# LedEsp32_rev1.net
KiCad netlist of a schematic drawn in EAGLE
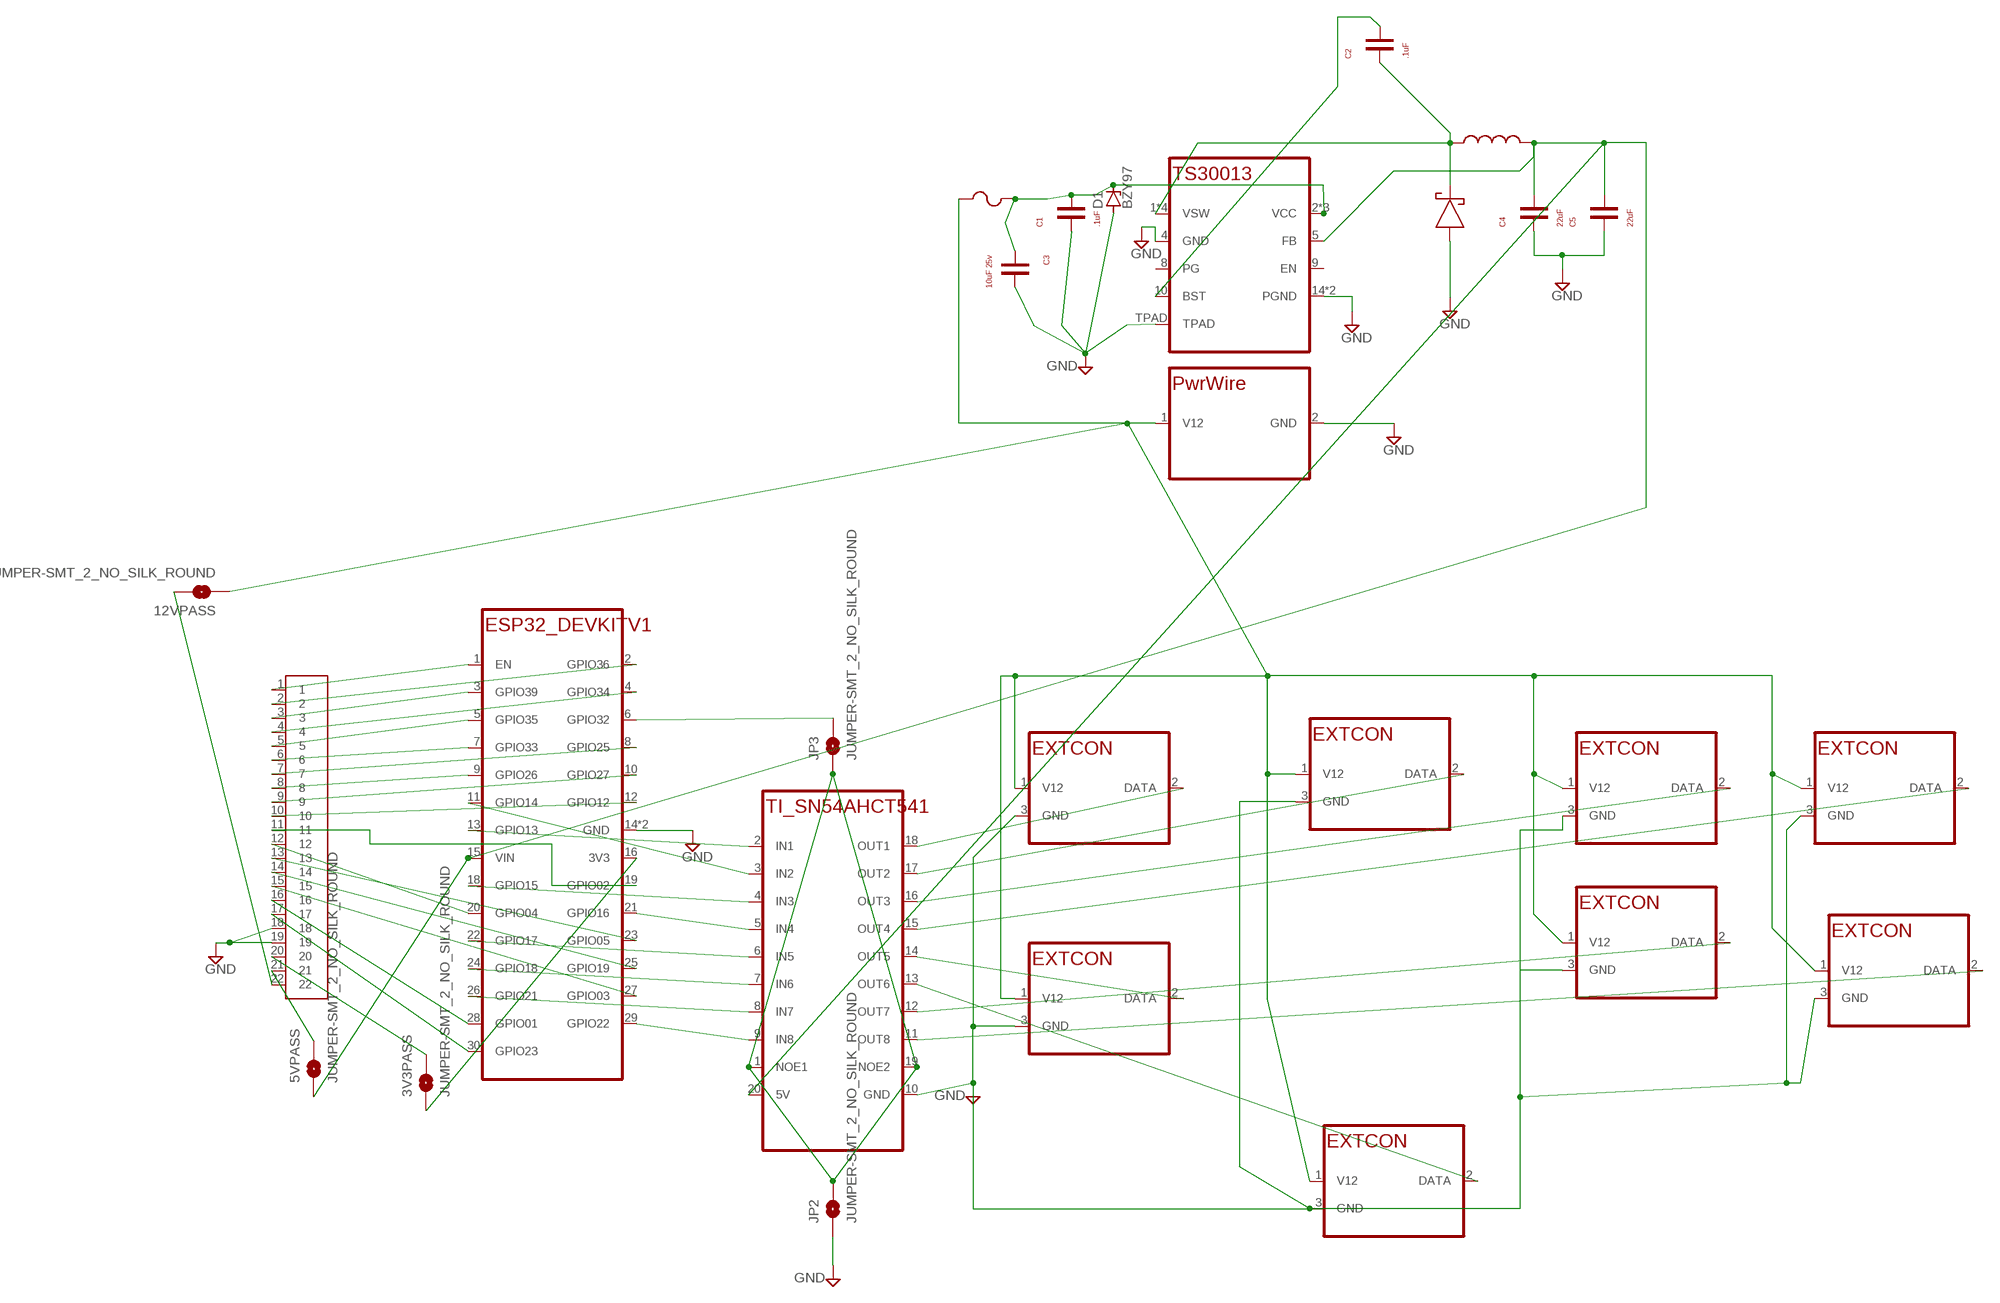
[diagram p0: schematic, sheet 1]

(export (version "E")
  (design (tool "Eeschema 10.0.6"))
  (components
    (comp (ref "3V3PASS")
      (value "JUMPER-SMT_2_NO_SILK_ROUND")
      (footprint "eagle-import:SMT-JUMPER_2_NO_SILK_ROUND")
      (libsource (lib "eagle-import") (part "JUMPER-SMT_2_NO_SILK_ROUND"))
    )
    (comp (ref "5VPASS")
      (value "JUMPER-SMT_2_NO_SILK_ROUND")
      (footprint "eagle-import:SMT-JUMPER_2_NO_SILK_ROUND")
      (libsource (lib "eagle-import") (part "JUMPER-SMT_2_NO_SILK_ROUND"))
    )
    (comp (ref "12VPASS")
      (value "JUMPER-SMT_2_NO_SILK_ROUND")
      (footprint "eagle-import:SMT-JUMPER_2_NO_SILK_ROUND")
      (libsource (lib "eagle-import") (part "JUMPER-SMT_2_NO_SILK_ROUND"))
    )
    (comp (ref "C1")
      (value ".1uF")
      (footprint "eagle-import:C0603")
      (libsource (lib "eagle-import") (part "CAPACITOR_NONPOLARC0603"))
    )
    (comp (ref "C2")
      (value ".1uF")
      (footprint "eagle-import:C0603")
      (libsource (lib "eagle-import") (part "CAPACITOR_NONPOLARC0603"))
    )
    (comp (ref "C3")
      (value "10uF 25v")
      (footprint "eagle-import:C1206")
      (libsource (lib "eagle-import") (part "CL31A106MAHNNNEC1206"))
    )
    (comp (ref "C4")
      (value "22uF")
      (footprint "eagle-import:C0603")
      (libsource (lib "eagle-import") (part "GRM188R61A226ME15DC0603"))
    )
    (comp (ref "C5")
      (value "22uF")
      (footprint "eagle-import:C0603")
      (libsource (lib "eagle-import") (part "GRM188R61A226ME15DC0603"))
    )
    (comp (ref "D1")
      (value "BZY97")
      (footprint "eagle-import:F126Z12")
      (libsource (lib "eagle-import") (part "BZY97"))
    )
    (comp (ref "D2")
      (value "LS54LS54")
      (footprint "eagle-import:LS54")
      (libsource (lib "eagle-import") (part "LS54LS54"))
    )
    (comp (ref "F1")
      (value "3A")
      (footprint "eagle-import:R0603")
      (libsource (lib "eagle-import") (part "FUSER0603"))
    )
    (comp (ref "IC1")
      (value "TS30013QFN16")
      (footprint "eagle-import:QFN16")
      (libsource (lib "eagle-import") (part "TS30013QFN16"))
    )
    (comp (ref "JP2")
      (value "JUMPER-SMT_2_NO_SILK_ROUND")
      (footprint "eagle-import:SMT-JUMPER_2_NO_SILK_ROUND")
      (libsource (lib "eagle-import") (part "JUMPER-SMT_2_NO_SILK_ROUND"))
    )
    (comp (ref "JP3")
      (value "JUMPER-SMT_2_NO_SILK_ROUND")
      (footprint "eagle-import:SMT-JUMPER_2_NO_SILK_ROUND")
      (libsource (lib "eagle-import") (part "JUMPER-SMT_2_NO_SILK_ROUND"))
    )
    (comp (ref "L1")
      (value "SRN5040TA-4R7MSRN5040TA")
      (footprint "eagle-import:SRN5040TA")
      (libsource (lib "eagle-import") (part "SRN5040TA-4R7MSRN5040TA"))
    )
    (comp (ref "LC$0")
      (value "EXTCONEXTCONDEVINST")
      (footprint "eagle-import:EXTCON")
      (libsource (lib "eagle-import") (part "EXTCONEXTCONDEVINST"))
    )
    (comp (ref "LC$1")
      (value "EXTCONEXTCONDEVINST")
      (footprint "eagle-import:EXTCON")
      (libsource (lib "eagle-import") (part "EXTCONEXTCONDEVINST"))
    )
    (comp (ref "LC$2")
      (value "EXTCONEXTCONDEVINST")
      (footprint "eagle-import:EXTCON")
      (libsource (lib "eagle-import") (part "EXTCONEXTCONDEVINST"))
    )
    (comp (ref "LC$3")
      (value "EXTCONEXTCONDEVINST")
      (footprint "eagle-import:EXTCON")
      (libsource (lib "eagle-import") (part "EXTCONEXTCONDEVINST"))
    )
    (comp (ref "LC$4")
      (value "EXTCONEXTCONDEVINST")
      (footprint "eagle-import:EXTCON")
      (libsource (lib "eagle-import") (part "EXTCONEXTCONDEVINST"))
    )
    (comp (ref "LC$5")
      (value "EXTCONEXTCONDEVINST")
      (footprint "eagle-import:EXTCON")
      (libsource (lib "eagle-import") (part "EXTCONEXTCONDEVINST"))
    )
    (comp (ref "LC$6")
      (value "EXTCONEXTCONDEVINST")
      (footprint "eagle-import:EXTCON")
      (libsource (lib "eagle-import") (part "EXTCONEXTCONDEVINST"))
    )
    (comp (ref "LC$7")
      (value "EXTCONEXTCONDEVINST")
      (footprint "eagle-import:EXTCON")
      (libsource (lib "eagle-import") (part "EXTCONEXTCONDEVINST"))
    )
    (comp (ref "U$1")
      (value "ESP32_DEVKITV1ESP32_DEVKITV1DEVINST")
      (footprint "eagle-import:ESP32_DEVKITV1")
      (libsource (lib "eagle-import") (part "ESP32_DEVKITV1ESP32_DEVKITV1DEVINST"))
    )
    (comp (ref "U$2")
      (value "TI_SN54AHCT541SO20WDEVINST")
      (footprint "eagle-import:SO20W")
      (libsource (lib "eagle-import") (part "TI_SN54AHCT541SO20WDEVINST"))
    )
    (comp (ref "U$3")
      (value "1X22THM")
      (footprint "eagle-import:1X22")
      (libsource (lib "eagle-import") (part "1X22THM"))
    )
    (comp (ref "U$8")
      (value "PWRWIREDPWRWIREP")
      (footprint "eagle-import:PWRWIREP")
      (libsource (lib "eagle-import") (part "PWRWIREDPWRWIREP"))
    )
  )
  (nets
    (net (code "1") (name "GND") (class "Default")
      (node (ref "C1") (pin "1") (pinfunction "1_1") (pintype "bidirectional"))
      (node (ref "C3") (pin "2") (pinfunction "2_2") (pintype "bidirectional"))
      (node (ref "C4") (pin "1") (pinfunction "1_1") (pintype "bidirectional"))
      (node (ref "C5") (pin "1") (pinfunction "1_1") (pintype "bidirectional"))
      (node (ref "D1") (pin "A") (pinfunction "A_A") (pintype "passive"))
      (node (ref "D2") (pin "1") (pinfunction "1_1") (pintype "bidirectional"))
      (node (ref "IC1") (pin "14") (pinfunction "PGND_14") (pintype "bidirectional"))
      (node (ref "IC1") (pin "15") (pinfunction "PGND_15") (pintype "bidirectional"))
      (node (ref "IC1") (pin "4") (pinfunction "GND_4") (pintype "bidirectional"))
      (node (ref "IC1") (pin "TPAD") (pinfunction "TPAD_TPAD") (pintype "bidirectional"))
      (node (ref "JP2") (pin "1") (pinfunction "1_1") (pintype "passive"))
      (node (ref "LC$0") (pin "3") (pinfunction "GND_3") (pintype "bidirectional"))
      (node (ref "LC$1") (pin "3") (pinfunction "GND_3") (pintype "bidirectional"))
      (node (ref "LC$2") (pin "3") (pinfunction "GND_3") (pintype "bidirectional"))
      (node (ref "LC$3") (pin "3") (pinfunction "GND_3") (pintype "bidirectional"))
      (node (ref "LC$4") (pin "3") (pinfunction "GND_3") (pintype "bidirectional"))
      (node (ref "LC$5") (pin "3") (pinfunction "GND_3") (pintype "bidirectional"))
      (node (ref "LC$6") (pin "3") (pinfunction "GND_3") (pintype "bidirectional"))
      (node (ref "LC$7") (pin "3") (pinfunction "GND_3") (pintype "bidirectional"))
      (node (ref "U$1") (pin "14") (pinfunction "GND_14") (pintype "bidirectional"))
      (node (ref "U$1") (pin "17") (pinfunction "GND_17") (pintype "bidirectional"))
      (node (ref "U$2") (pin "10") (pinfunction "GND_10") (pintype "bidirectional"))
      (node (ref "U$3") (pin "18") (pinfunction "18_18") (pintype "bidirectional"))
      (node (ref "U$3") (pin "19") (pinfunction "19_19") (pintype "bidirectional"))
      (node (ref "U$8") (pin "2") (pinfunction "GND_2") (pintype "bidirectional"))
    )
    (net (code "2") (name "Net-(3V3PASS-Pad2)") (class "Default")
      (node (ref "3V3PASS") (pin "2") (pinfunction "2_2") (pintype "passive"))
      (node (ref "U$3") (pin "20") (pinfunction "20_20") (pintype "bidirectional"))
    )
    (net (code "3") (name "Net-(5VPASS-Pad2)") (class "Default")
      (node (ref "5VPASS") (pin "2") (pinfunction "2_2") (pintype "passive"))
      (node (ref "U$3") (pin "21") (pinfunction "21_21") (pintype "bidirectional"))
    )
    (net (code "4") (name "Net-(12VPASS-Pad2)") (class "Default")
      (node (ref "12VPASS") (pin "2") (pinfunction "2_2") (pintype "passive"))
      (node (ref "U$3") (pin "22") (pinfunction "22_22") (pintype "bidirectional"))
    )
    (net (code "5") (name "Net-(C1-Pad2)") (class "Default")
      (node (ref "C1") (pin "2") (pinfunction "2_2") (pintype "bidirectional"))
      (node (ref "C3") (pin "1") (pinfunction "1_1") (pintype "bidirectional"))
      (node (ref "D1") (pin "C") (pinfunction "C_C") (pintype "passive"))
      (node (ref "F1") (pin "2") (pinfunction "2_2") (pintype "bidirectional"))
      (node (ref "IC1") (pin "11") (pinfunction "VCC_11") (pintype "bidirectional"))
      (node (ref "IC1") (pin "2") (pinfunction "VCC_2") (pintype "bidirectional"))
      (node (ref "IC1") (pin "3") (pinfunction "VCC_3") (pintype "bidirectional"))
    )
    (net (code "6") (name "Net-(C2-Pad1)") (class "Default")
      (node (ref "C2") (pin "1") (pinfunction "1_1") (pintype "bidirectional"))
      (node (ref "D2") (pin "2") (pinfunction "2_2") (pintype "bidirectional"))
      (node (ref "IC1") (pin "1") (pinfunction "VSW_1") (pintype "bidirectional"))
      (node (ref "IC1") (pin "12") (pinfunction "VSW_12") (pintype "bidirectional"))
      (node (ref "IC1") (pin "13") (pinfunction "VSW_13") (pintype "bidirectional"))
      (node (ref "IC1") (pin "16") (pinfunction "VSW_16") (pintype "bidirectional"))
      (node (ref "L1") (pin "1") (pinfunction "1_1") (pintype "bidirectional"))
    )
    (net (code "7") (name "Net-(IC1-BST)") (class "Default")
      (node (ref "C2") (pin "2") (pinfunction "2_2") (pintype "bidirectional"))
      (node (ref "IC1") (pin "10") (pinfunction "BST_10") (pintype "bidirectional"))
    )
    (net (code "8") (name "Net-(IC1-FB)") (class "Default")
      (node (ref "5VPASS") (pin "1") (pinfunction "1_1") (pintype "passive"))
      (node (ref "C4") (pin "2") (pinfunction "2_2") (pintype "bidirectional"))
      (node (ref "C5") (pin "2") (pinfunction "2_2") (pintype "bidirectional"))
      (node (ref "IC1") (pin "5") (pinfunction "FB_5") (pintype "bidirectional"))
      (node (ref "L1") (pin "2") (pinfunction "2_2") (pintype "bidirectional"))
      (node (ref "U$1") (pin "15") (pinfunction "VIN_15") (pintype "bidirectional"))
      (node (ref "U$2") (pin "20") (pinfunction "5V_20") (pintype "bidirectional"))
    )
    (net (code "9") (name "Net-(LC$0-DATA)") (class "Default")
      (node (ref "LC$0") (pin "2") (pinfunction "DATA_2") (pintype "bidirectional"))
      (node (ref "U$2") (pin "18") (pinfunction "OUT1_18") (pintype "bidirectional"))
    )
    (net (code "10") (name "Net-(LC$0-V12)") (class "Default")
      (node (ref "12VPASS") (pin "1") (pinfunction "1_1") (pintype "passive"))
      (node (ref "F1") (pin "1") (pinfunction "1_1") (pintype "bidirectional"))
      (node (ref "LC$0") (pin "1") (pinfunction "V12_1") (pintype "bidirectional"))
      (node (ref "LC$1") (pin "1") (pinfunction "V12_1") (pintype "bidirectional"))
      (node (ref "LC$2") (pin "1") (pinfunction "V12_1") (pintype "bidirectional"))
      (node (ref "LC$3") (pin "1") (pinfunction "V12_1") (pintype "bidirectional"))
      (node (ref "LC$4") (pin "1") (pinfunction "V12_1") (pintype "bidirectional"))
      (node (ref "LC$5") (pin "1") (pinfunction "V12_1") (pintype "bidirectional"))
      (node (ref "LC$6") (pin "1") (pinfunction "V12_1") (pintype "bidirectional"))
      (node (ref "LC$7") (pin "1") (pinfunction "V12_1") (pintype "bidirectional"))
      (node (ref "U$8") (pin "1") (pinfunction "V12_1") (pintype "bidirectional"))
    )
    (net (code "11") (name "Net-(LC$1-DATA)") (class "Default")
      (node (ref "LC$1") (pin "2") (pinfunction "DATA_2") (pintype "bidirectional"))
      (node (ref "U$2") (pin "17") (pinfunction "OUT2_17") (pintype "bidirectional"))
    )
    (net (code "12") (name "Net-(LC$2-DATA)") (class "Default")
      (node (ref "LC$2") (pin "2") (pinfunction "DATA_2") (pintype "bidirectional"))
      (node (ref "U$2") (pin "16") (pinfunction "OUT3_16") (pintype "bidirectional"))
    )
    (net (code "13") (name "Net-(LC$3-DATA)") (class "Default")
      (node (ref "LC$3") (pin "2") (pinfunction "DATA_2") (pintype "bidirectional"))
      (node (ref "U$2") (pin "15") (pinfunction "OUT4_15") (pintype "bidirectional"))
    )
    (net (code "14") (name "Net-(LC$4-DATA)") (class "Default")
      (node (ref "LC$4") (pin "2") (pinfunction "DATA_2") (pintype "bidirectional"))
      (node (ref "U$2") (pin "14") (pinfunction "OUT5_14") (pintype "bidirectional"))
    )
    (net (code "15") (name "Net-(LC$5-DATA)") (class "Default")
      (node (ref "LC$5") (pin "2") (pinfunction "DATA_2") (pintype "bidirectional"))
      (node (ref "U$2") (pin "13") (pinfunction "OUT6_13") (pintype "bidirectional"))
    )
    (net (code "16") (name "Net-(LC$6-DATA)") (class "Default")
      (node (ref "LC$6") (pin "2") (pinfunction "DATA_2") (pintype "bidirectional"))
      (node (ref "U$2") (pin "12") (pinfunction "OUT7_12") (pintype "bidirectional"))
    )
    (net (code "17") (name "Net-(LC$7-DATA)") (class "Default")
      (node (ref "LC$7") (pin "2") (pinfunction "DATA_2") (pintype "bidirectional"))
      (node (ref "U$2") (pin "11") (pinfunction "OUT8_11") (pintype "bidirectional"))
    )
    (net (code "18") (name "Net-(U$1-3V3)") (class "Default")
      (node (ref "3V3PASS") (pin "1") (pinfunction "1_1") (pintype "passive"))
      (node (ref "U$1") (pin "16") (pinfunction "3V3_16") (pintype "bidirectional"))
    )
    (net (code "19") (name "Net-(U$1-EN)") (class "Default")
      (node (ref "U$1") (pin "1") (pinfunction "EN_1") (pintype "bidirectional"))
      (node (ref "U$3") (pin "1") (pinfunction "1_1") (pintype "bidirectional"))
    )
    (net (code "20") (name "Net-(U$1-GPIO01)") (class "Default")
      (node (ref "U$1") (pin "28") (pinfunction "GPIO01_28") (pintype "bidirectional"))
      (node (ref "U$3") (pin "16") (pinfunction "16_16") (pintype "bidirectional"))
    )
    (net (code "21") (name "Net-(U$1-GPIO02)") (class "Default")
      (node (ref "U$1") (pin "19") (pinfunction "GPIO02_19") (pintype "bidirectional"))
      (node (ref "U$3") (pin "11") (pinfunction "11_11") (pintype "bidirectional"))
    )
    (net (code "22") (name "Net-(U$1-GPIO03)") (class "Default")
      (node (ref "U$1") (pin "27") (pinfunction "GPIO03_27") (pintype "bidirectional"))
      (node (ref "U$3") (pin "15") (pinfunction "15_15") (pintype "bidirectional"))
    )
    (net (code "23") (name "Net-(U$1-GPIO04)") (class "Default")
      (node (ref "U$1") (pin "20") (pinfunction "GPIO04_20") (pintype "bidirectional"))
      (node (ref "U$3") (pin "12") (pinfunction "12_12") (pintype "bidirectional"))
    )
    (net (code "24") (name "Net-(U$1-GPIO05)") (class "Default")
      (node (ref "U$1") (pin "23") (pinfunction "GPIO05_23") (pintype "bidirectional"))
      (node (ref "U$3") (pin "13") (pinfunction "13_13") (pintype "bidirectional"))
    )
    (net (code "25") (name "Net-(U$1-GPIO12)") (class "Default")
      (node (ref "U$1") (pin "12") (pinfunction "GPIO12_12") (pintype "bidirectional"))
      (node (ref "U$3") (pin "10") (pinfunction "10_10") (pintype "bidirectional"))
    )
    (net (code "26") (name "Net-(U$1-GPIO13)") (class "Default")
      (node (ref "U$1") (pin "13") (pinfunction "GPIO13_13") (pintype "bidirectional"))
      (node (ref "U$2") (pin "2") (pinfunction "IN1_2") (pintype "bidirectional"))
    )
    (net (code "27") (name "Net-(U$1-GPIO14)") (class "Default")
      (node (ref "U$1") (pin "11") (pinfunction "GPIO14_11") (pintype "bidirectional"))
      (node (ref "U$2") (pin "3") (pinfunction "IN2_3") (pintype "bidirectional"))
    )
    (net (code "28") (name "Net-(U$1-GPIO15)") (class "Default")
      (node (ref "U$1") (pin "18") (pinfunction "GPIO15_18") (pintype "bidirectional"))
      (node (ref "U$2") (pin "4") (pinfunction "IN3_4") (pintype "bidirectional"))
    )
    (net (code "29") (name "Net-(U$1-GPIO16)") (class "Default")
      (node (ref "U$1") (pin "21") (pinfunction "GPIO16_21") (pintype "bidirectional"))
      (node (ref "U$2") (pin "5") (pinfunction "IN4_5") (pintype "bidirectional"))
    )
    (net (code "30") (name "Net-(U$1-GPIO17)") (class "Default")
      (node (ref "U$1") (pin "22") (pinfunction "GPIO17_22") (pintype "bidirectional"))
      (node (ref "U$2") (pin "6") (pinfunction "IN5_6") (pintype "bidirectional"))
    )
    (net (code "31") (name "Net-(U$1-GPIO18)") (class "Default")
      (node (ref "U$1") (pin "24") (pinfunction "GPIO18_24") (pintype "bidirectional"))
      (node (ref "U$2") (pin "7") (pinfunction "IN6_7") (pintype "bidirectional"))
    )
    (net (code "32") (name "Net-(U$1-GPIO19)") (class "Default")
      (node (ref "U$1") (pin "25") (pinfunction "GPIO19_25") (pintype "bidirectional"))
      (node (ref "U$3") (pin "14") (pinfunction "14_14") (pintype "bidirectional"))
    )
    (net (code "33") (name "Net-(U$1-GPIO21)") (class "Default")
      (node (ref "U$1") (pin "26") (pinfunction "GPIO21_26") (pintype "bidirectional"))
      (node (ref "U$2") (pin "8") (pinfunction "IN7_8") (pintype "bidirectional"))
    )
    (net (code "34") (name "Net-(U$1-GPIO22)") (class "Default")
      (node (ref "U$1") (pin "29") (pinfunction "GPIO22_29") (pintype "bidirectional"))
      (node (ref "U$2") (pin "9") (pinfunction "IN8_9") (pintype "bidirectional"))
    )
    (net (code "35") (name "Net-(U$1-GPIO23)") (class "Default")
      (node (ref "U$1") (pin "30") (pinfunction "GPIO23_30") (pintype "bidirectional"))
      (node (ref "U$3") (pin "17") (pinfunction "17_17") (pintype "bidirectional"))
    )
    (net (code "36") (name "Net-(U$1-GPIO25)") (class "Default")
      (node (ref "U$1") (pin "8") (pinfunction "GPIO25_8") (pintype "bidirectional"))
      (node (ref "U$3") (pin "7") (pinfunction "7_7") (pintype "bidirectional"))
    )
    (net (code "37") (name "Net-(U$1-GPIO26)") (class "Default")
      (node (ref "U$1") (pin "9") (pinfunction "GPIO26_9") (pintype "bidirectional"))
      (node (ref "U$3") (pin "8") (pinfunction "8_8") (pintype "bidirectional"))
    )
    (net (code "38") (name "Net-(U$1-GPIO27)") (class "Default")
      (node (ref "U$1") (pin "10") (pinfunction "GPIO27_10") (pintype "bidirectional"))
      (node (ref "U$3") (pin "9") (pinfunction "9_9") (pintype "bidirectional"))
    )
    (net (code "39") (name "Net-(U$1-GPIO32)") (class "Default")
      (node (ref "JP3") (pin "2") (pinfunction "2_2") (pintype "passive"))
      (node (ref "U$1") (pin "6") (pinfunction "GPIO32_6") (pintype "bidirectional"))
    )
    (net (code "40") (name "Net-(U$1-GPIO33)") (class "Default")
      (node (ref "U$1") (pin "7") (pinfunction "GPIO33_7") (pintype "bidirectional"))
      (node (ref "U$3") (pin "6") (pinfunction "6_6") (pintype "bidirectional"))
    )
    (net (code "41") (name "Net-(U$1-GPIO34)") (class "Default")
      (node (ref "U$1") (pin "4") (pinfunction "GPIO34_4") (pintype "bidirectional"))
      (node (ref "U$3") (pin "4") (pinfunction "4_4") (pintype "bidirectional"))
    )
    (net (code "42") (name "Net-(U$1-GPIO35)") (class "Default")
      (node (ref "U$1") (pin "5") (pinfunction "GPIO35_5") (pintype "bidirectional"))
      (node (ref "U$3") (pin "5") (pinfunction "5_5") (pintype "bidirectional"))
    )
    (net (code "43") (name "Net-(U$1-GPIO36)") (class "Default")
      (node (ref "U$1") (pin "2") (pinfunction "GPIO36_2") (pintype "bidirectional"))
      (node (ref "U$3") (pin "2") (pinfunction "2_2") (pintype "bidirectional"))
    )
    (net (code "44") (name "Net-(U$1-GPIO39)") (class "Default")
      (node (ref "U$1") (pin "3") (pinfunction "GPIO39_3") (pintype "bidirectional"))
      (node (ref "U$3") (pin "3") (pinfunction "3_3") (pintype "bidirectional"))
    )
    (net (code "45") (name "Net-(U$2-NOE1)") (class "Default")
      (node (ref "JP2") (pin "2") (pinfunction "2_2") (pintype "passive"))
      (node (ref "JP3") (pin "1") (pinfunction "1_1") (pintype "passive"))
      (node (ref "U$2") (pin "1") (pinfunction "NOE1_1") (pintype "bidirectional"))
      (node (ref "U$2") (pin "19") (pinfunction "NOE2_19") (pintype "bidirectional"))
    )
    (net (code "46") (name "unconnected-(IC1-EN-Pad9)") (class "Default")
      (node (ref "IC1") (pin "9") (pinfunction "EN_9") (pintype "bidirectional"))
    )
    (net (code "47") (name "unconnected-(IC1-PG-Pad8)") (class "Default")
      (node (ref "IC1") (pin "8") (pinfunction "PG_8") (pintype "bidirectional"))
    )
  )
)
